# Esp32-S3-Mainboard.net
KiCad netlist of a schematic drawn in Altium Designer
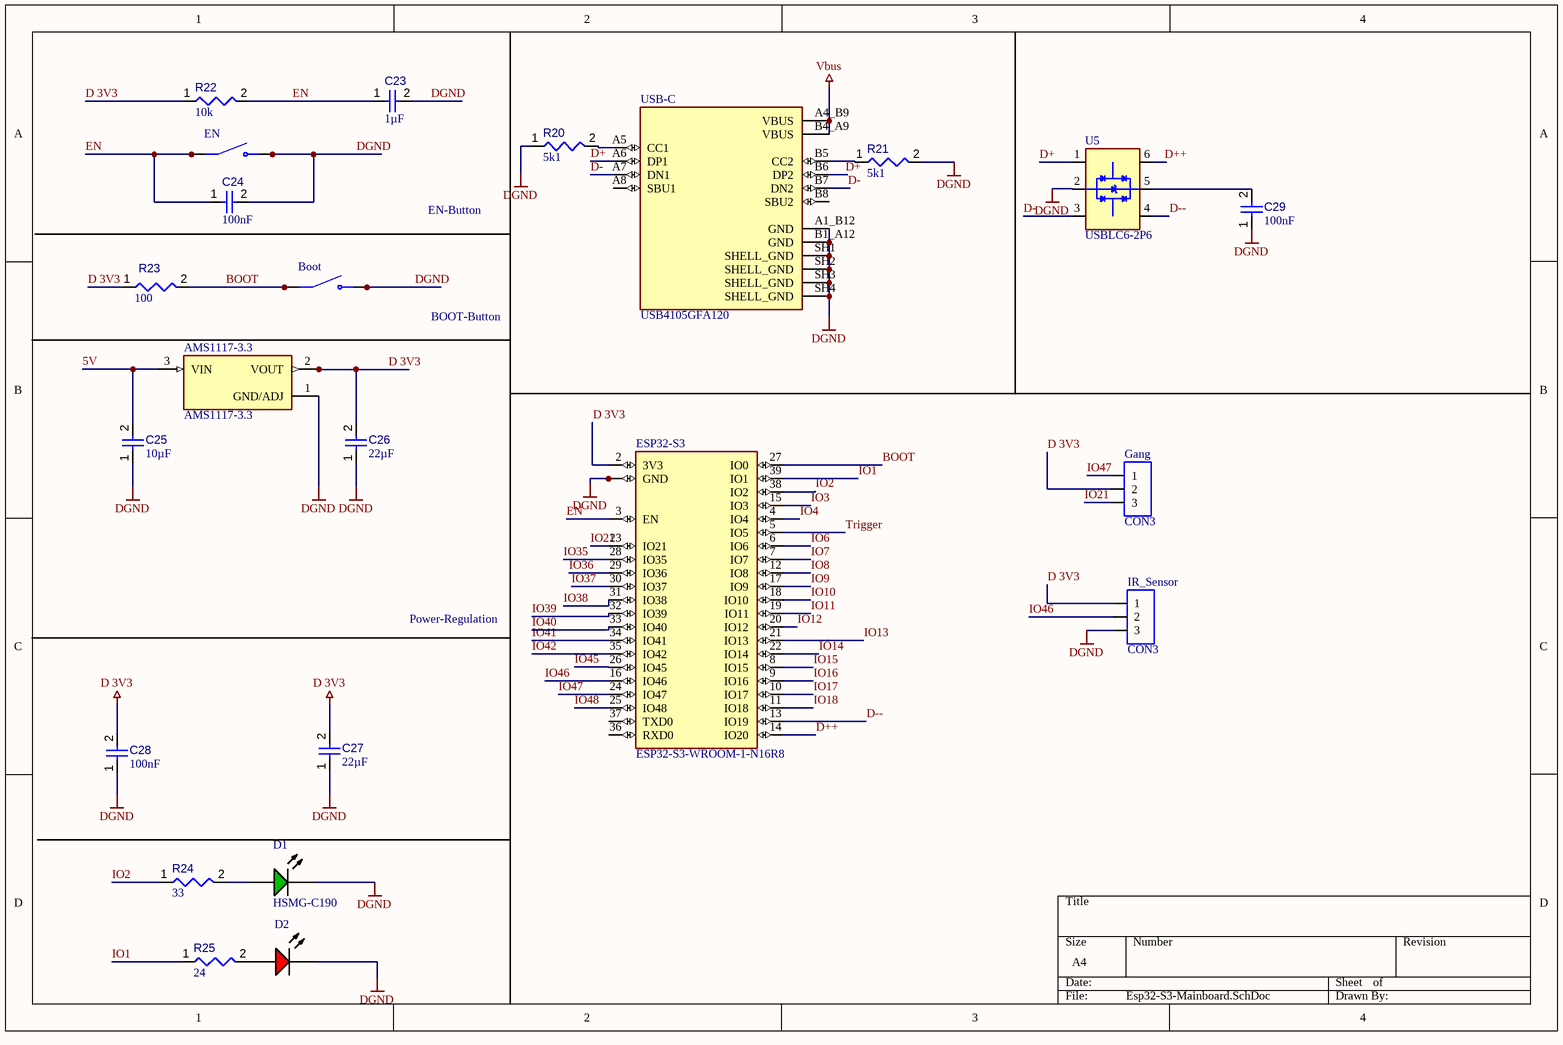
[diagram p0: Esp32-S3-Mainboard.SchDoc]

(export (version "E")
  (design (tool "Eeschema 10.0.6"))
  (components
    (comp (ref "AMS1117-3.3")
      (value "AMS1117-3.3")
      (footprint "SOT229P700X180-4N")
      (description "LDO Voltage Regulators 800MA LDO LINEAR REG")
      (fields (field (name "MF") "ams AG"))
      (libsource (lib "AMS1117-3.3") (part "AMS1117-3.3"))
    )
    (comp (ref "Boot")
      (value "FSM2JSMLTR")
      (footprint "SW_1571527-2")
      (description "Switch Tactile OFF (ON) SPST Round Button Gull Wing 0.05A 24VDC 0.98N SMD T/R")
      (fields (field (name "MF") "TE Connectivity"))
      (libsource (lib " L-PRAN") (part "FSM2JSMLTR"))
    )
    (comp (ref "C23")
      (value "1µF")
      (footprint "CAPC1608X90X35ML15T15")
      (description "Chip Capacitor, 1 uF, +/- 10%, 16 V, 0603 (1608 Metric)")
      (fields (field (name "TOLERANCE") "10%") (field (name "Comment") "Capacitor 1uF +/- 10% 16V 0603"))
      (libsource (lib " L-PRAN") (part "CAP-NP-2"))
    )
    (comp (ref "C24")
      (value "100nF")
      (footprint "CAPC1608X90X40NL10T20")
      (description "Chip Capacitor, 100 nF, +/- 10%, 50 V, 0603 (1608 Metric)")
      (fields (field (name "TOLERANCE") "10%") (field (name "Comment") "Capacitor 100 nF +/-10% 50 V 0603"))
      (libsource (lib " L-PRAN") (part "CAP-NP-2"))
    )
    (comp (ref "C25")
      (value "10µF")
      (footprint "CAPC0603(1608)100_L")
      (description "Chip Capacitor, 10µF +/-20%, 10V, 0603, Thickness 1 mm")
      (fields (field (name "TOLERANCE") "10%") (field (name "Comment") "Capacitor 10µF +/-20% 10V 0603"))
      (libsource (lib " L-PRAN") (part "CAP-NP-2"))
    )
    (comp (ref "C26")
      (value "22µF")
      (footprint "CAPC0805(2012)145_L")
      (description "Chip Capacitor, 22µF +/-40%, 16V, 0805, Thickness 1.45 mm")
      (fields (field (name "TOLERANCE") "5%") (field (name "Comment") "Capacitor 22µF +/-40% 16V 0805"))
      (libsource (lib " L-PRAN") (part "CAP-NP-2"))
    )
    (comp (ref "C27")
      (value "22µF")
      (footprint "CAPC0805(2012)145_L")
      (description "Chip Capacitor, 22µF +/-40%, 16V, 0805, Thickness 1.45 mm")
      (fields (field (name "TOLERANCE") "5%") (field (name "Comment") "Capacitor 22µF +/-40% 16V 0805"))
      (libsource (lib " L-PRAN") (part "CAP-NP-2"))
    )
    (comp (ref "C28")
      (value "100nF")
      (footprint "CAPC1608X90X40NL10T20")
      (description "Chip Capacitor, 100 nF, +/- 10%, 50 V, 0603 (1608 Metric)")
      (fields (field (name "TOLERANCE") "10%") (field (name "Comment") "Capacitor 100 nF +/-10% 50 V 0603"))
      (libsource (lib " L-PRAN") (part "CAP-NP-2"))
    )
    (comp (ref "C29")
      (value "100nF")
      (footprint "CAPC0402(1005)60_L")
      (description "Chip Capacitor, 100nF +/-20%, 50V, 0402, Thickness 0.6 mm")
      (fields (field (name "TOLERANCE") "10%") (field (name "Comment") "Capacitor 100nF +/-20% 50V 0402"))
      (libsource (lib " L-PRAN") (part "CAP-NP-2"))
    )
    (comp (ref "D1")
      (value "HSMG-C190")
      (footprint "AVAG-HSMX-C190_V")
      (description "LED Uni-Color Green, 52 mW, 20 mA, -40 to 85 degC, 2-Pin SMD, RoHS, Tape and Reel")
      (fields (field (name "POWER") "52mW") (field (name "MANUFACTURER") "Avago"))
      (libsource (lib " L-PRAN") (part "LED-GREEN-AK-2"))
    )
    (comp (ref "D2")
      (value "19-217/R6C-AL1M2VY/3T")
      (footprint "EVRL-0603-2_V")
      (description "Chip LED, Red, 5 V, 25 mA, -40 to 85 degC, 2-Pin SMD (0603), RoHS, Tape and Reel")
      (fields (field (name "MANUFACTURER") "Everlight Electronics"))
      (libsource (lib " L-PRAN") (part "LED-RED-AK-2"))
    )
    (comp (ref "EN")
      (value "FSM2JSMLTR")
      (footprint "SW_1571527-2")
      (description "Switch Tactile OFF (ON) SPST Round Button Gull Wing 0.05A 24VDC 0.98N SMD T/R")
      (fields (field (name "MF") "TE Connectivity"))
      (libsource (lib " L-PRAN") (part "FSM2JSMLTR"))
    )
    (comp (ref "ESP32-S3")
      (value "ESP32-S3-WROOM-1-N16R8")
      (footprint "ESP32S3WROOM1N8R2")
      (description "Bluetooth, WiFi 802.11b/g/n, Bluetooth v5.0 Transceiver Module 2.4GHz PCB Trace Surface Mount")
      (fields (field (name "MF") "Espressif Systems"))
      (libsource (lib "ESP32-S3-WROOM-1-N16R8") (part "ESP32-S3-WROOM-1-N16R8"))
    )
    (comp (ref "Gang")
      (value "CON3")
      (footprint "Sip-3")
      (description "Stecker")
      (libsource (lib "HTL-sym-2021_04") (part "CON3"))
    )
    (comp (ref "IR_Sensor")
      (value "CON3")
      (footprint "Sip-3")
      (description "Stecker")
      (libsource (lib "HTL-sym-2021_04") (part "CON3"))
    )
    (comp (ref "R20")
      (value "5k1")
      (footprint "RESC1608X55X25ML10T15")
      (description "Chip Resistor, 100 KOhm, +/- 1%, 0.1 W, -55 to 155 degC, 0603 (1608 Metric)")
      (fields (field (name "TOLERANCE") "1%") (field (name "POWER") "100mW"))
      (libsource (lib " L-PRAN") (part "RES-2"))
    )
    (comp (ref "R21")
      (value "5k1")
      (footprint "RESC1608X55X25ML10T15")
      (description "Chip Resistor, 100 KOhm, +/- 1%, 0.1 W, -55 to 155 degC, 0603 (1608 Metric)")
      (fields (field (name "TOLERANCE") "1%") (field (name "POWER") "100mW"))
      (libsource (lib " L-PRAN") (part "RES-2"))
    )
    (comp (ref "R22")
      (value "10k")
      (footprint "RESC1608X55X25ML10T15")
      (description "Chip Resistor, 10 KOhm, +/- 1%, 01 W, -55 to 155 degC, 0603 (1608 Metric)")
      (fields (field (name "POWER") "100mW") (field (name "TOLERANCE") "1%"))
      (libsource (lib " L-PRAN") (part "RES-2"))
    )
    (comp (ref "R23")
      (value "100")
      (footprint "RESC1608X55X25ML10T15")
      (description "Chip Resistor, 10 KOhm, +/- 1%, 01 W, -55 to 155 degC, 0603 (1608 Metric)")
      (fields (field (name "POWER") "100mW") (field (name "TOLERANCE") "1%"))
      (libsource (lib " L-PRAN") (part "RES-2"))
    )
    (comp (ref "R24")
      (value "33")
      (footprint "RESC1608X55X25ML10T15")
      (description "Chip Resistor, 10 KOhm, +/- 1%, 01 W, -55 to 155 degC, 0603 (1608 Metric)")
      (fields (field (name "POWER") "100mW") (field (name "TOLERANCE") "1%"))
      (libsource (lib " L-PRAN") (part "RES-2"))
    )
    (comp (ref "R25")
      (value "24")
      (footprint "RESC1608X55X25ML10T15")
      (description "Chip Resistor, 10 KOhm, +/- 1%, 01 W, -55 to 155 degC, 0603 (1608 Metric)")
      (fields (field (name "POWER") "100mW") (field (name "TOLERANCE") "1%"))
      (libsource (lib " L-PRAN") (part "RES-2"))
    )
    (comp (ref "U5")
      (value "USBLC6-2P6")
      (footprint "SOT50P160X60-6N")
      (description "17V Clamp 5A (8/20Âµs) Ipp Tvs Diode Surface Mount SOT-666")
      (fields (field (name "MF") "STMicroelectronics"))
      (libsource (lib "USBLC6-2P6") (part "USBLC6-2P6"))
    )
    (comp (ref "USB-C")
      (value "USB4105GFA120")
      (footprint "GCT_USB4105GFA120")
      (fields (field (name "MF") "Global Connector Technology"))
      (libsource (lib "USB4105GFA120") (part "USB4105GFA120"))
    )
  )
  (nets
    (net (code "1") (name "/5V") (class "Default")
      (node (ref "AMS1117-3.3") (pin "3") (pinfunction "VIN_3") (pintype "input"))
      (node (ref "C25") (pin "2") (pinfunction "2_2") (pintype "passive"))
    )
    (net (code "2") (name "/BOOT") (class "Default")
      (node (ref "Boot") (pin "1") (pinfunction "COM_1") (pintype "passive"))
      (node (ref "Boot") (pin "2") (pinfunction "COM_2") (pintype "passive"))
      (node (ref "ESP32-S3") (pin "27") (pinfunction "IO0_27") (pintype "bidirectional"))
      (node (ref "R23") (pin "2") (pinfunction "2_2") (pintype "passive"))
    )
    (net (code "3") (name "/D+") (class "Default")
      (node (ref "U5") (pin "1") (pinfunction "I/O1_1_1") (pintype "bidirectional"))
      (node (ref "USB-C") (pin "A6") (pinfunction "DP1_A6") (pintype "bidirectional"))
      (node (ref "USB-C") (pin "B6") (pinfunction "DP2_B6") (pintype "bidirectional"))
    )
    (net (code "4") (name "/D++") (class "Default")
      (node (ref "ESP32-S3") (pin "14") (pinfunction "IO20_14") (pintype "bidirectional"))
      (node (ref "U5") (pin "6") (pinfunction "I/O1_2_6") (pintype "bidirectional"))
    )
    (net (code "5") (name "/D-") (class "Default")
      (node (ref "U5") (pin "3") (pinfunction "I/O2_1_3") (pintype "bidirectional"))
      (node (ref "USB-C") (pin "A7") (pinfunction "DN1_A7") (pintype "bidirectional"))
      (node (ref "USB-C") (pin "B7") (pinfunction "DN2_B7") (pintype "bidirectional"))
    )
    (net (code "6") (name "/D--") (class "Default")
      (node (ref "ESP32-S3") (pin "13") (pinfunction "IO19_13") (pintype "bidirectional"))
      (node (ref "U5") (pin "4") (pinfunction "I/O2_2_4") (pintype "bidirectional"))
    )
    (net (code "7") (name "/EN") (class "Default")
      (node (ref "C23") (pin "1") (pinfunction "1_1") (pintype "passive"))
      (node (ref "C24") (pin "1") (pinfunction "1_1") (pintype "passive"))
      (node (ref "EN") (pin "1") (pinfunction "COM_1") (pintype "passive"))
      (node (ref "EN") (pin "2") (pinfunction "COM_2") (pintype "passive"))
      (node (ref "ESP32-S3") (pin "3") (pinfunction "EN_3") (pintype "bidirectional"))
      (node (ref "R22") (pin "2") (pinfunction "2_2") (pintype "passive"))
    )
    (net (code "8") (name "/IO1") (class "Default")
      (node (ref "ESP32-S3") (pin "39") (pinfunction "IO1_39") (pintype "bidirectional"))
      (node (ref "R25") (pin "1") (pinfunction "1_1") (pintype "passive"))
    )
    (net (code "9") (name "/IO2") (class "Default")
      (node (ref "ESP32-S3") (pin "38") (pinfunction "IO2_38") (pintype "bidirectional"))
      (node (ref "R24") (pin "1") (pinfunction "1_1") (pintype "passive"))
    )
    (net (code "10") (name "/IO3") (class "Default")
      (node (ref "ESP32-S3") (pin "15") (pinfunction "IO3_15") (pintype "bidirectional"))
    )
    (net (code "11") (name "/IO4") (class "Default")
      (node (ref "ESP32-S3") (pin "4") (pinfunction "IO4_4") (pintype "bidirectional"))
    )
    (net (code "12") (name "/IO6") (class "Default")
      (node (ref "ESP32-S3") (pin "6") (pinfunction "IO6_6") (pintype "bidirectional"))
    )
    (net (code "13") (name "/IO7") (class "Default")
      (node (ref "ESP32-S3") (pin "7") (pinfunction "IO7_7") (pintype "bidirectional"))
    )
    (net (code "14") (name "/IO8") (class "Default")
      (node (ref "ESP32-S3") (pin "12") (pinfunction "IO8_12") (pintype "bidirectional"))
    )
    (net (code "15") (name "/IO9") (class "Default")
      (node (ref "ESP32-S3") (pin "17") (pinfunction "IO9_17") (pintype "bidirectional"))
    )
    (net (code "16") (name "/IO10") (class "Default")
      (node (ref "ESP32-S3") (pin "18") (pinfunction "IO10_18") (pintype "bidirectional"))
    )
    (net (code "17") (name "/IO11") (class "Default")
      (node (ref "ESP32-S3") (pin "19") (pinfunction "IO11_19") (pintype "bidirectional"))
    )
    (net (code "18") (name "/IO12") (class "Default")
      (node (ref "ESP32-S3") (pin "20") (pinfunction "IO12_20") (pintype "bidirectional"))
    )
    (net (code "19") (name "/IO13") (class "Default")
      (node (ref "ESP32-S3") (pin "21") (pinfunction "IO13_21") (pintype "bidirectional"))
    )
    (net (code "20") (name "/IO14") (class "Default")
      (node (ref "ESP32-S3") (pin "22") (pinfunction "IO14_22") (pintype "bidirectional"))
    )
    (net (code "21") (name "/IO15") (class "Default")
      (node (ref "ESP32-S3") (pin "8") (pinfunction "IO15_8") (pintype "bidirectional"))
    )
    (net (code "22") (name "/IO16") (class "Default")
      (node (ref "ESP32-S3") (pin "9") (pinfunction "IO16_9") (pintype "bidirectional"))
    )
    (net (code "23") (name "/IO17") (class "Default")
      (node (ref "ESP32-S3") (pin "10") (pinfunction "IO17_10") (pintype "bidirectional"))
    )
    (net (code "24") (name "/IO18") (class "Default")
      (node (ref "ESP32-S3") (pin "11") (pinfunction "IO18_11") (pintype "bidirectional"))
    )
    (net (code "25") (name "/IO21") (class "Default")
      (node (ref "ESP32-S3") (pin "23") (pinfunction "IO21_23") (pintype "bidirectional"))
      (node (ref "Gang") (pin "3") (pinfunction "3_3") (pintype "passive"))
    )
    (net (code "26") (name "/IO35") (class "Default")
      (node (ref "ESP32-S3") (pin "28") (pinfunction "IO35_28") (pintype "bidirectional"))
    )
    (net (code "27") (name "/IO36") (class "Default")
      (node (ref "ESP32-S3") (pin "29") (pinfunction "IO36_29") (pintype "bidirectional"))
    )
    (net (code "28") (name "/IO37") (class "Default")
      (node (ref "ESP32-S3") (pin "30") (pinfunction "IO37_30") (pintype "bidirectional"))
    )
    (net (code "29") (name "/IO38") (class "Default")
      (node (ref "ESP32-S3") (pin "31") (pinfunction "IO38_31") (pintype "bidirectional"))
    )
    (net (code "30") (name "/IO39") (class "Default")
      (node (ref "ESP32-S3") (pin "32") (pinfunction "IO39_32") (pintype "bidirectional"))
    )
    (net (code "31") (name "/IO40") (class "Default")
      (node (ref "ESP32-S3") (pin "33") (pinfunction "IO40_33") (pintype "bidirectional"))
    )
    (net (code "32") (name "/IO41") (class "Default")
      (node (ref "ESP32-S3") (pin "34") (pinfunction "IO41_34") (pintype "bidirectional"))
    )
    (net (code "33") (name "/IO42") (class "Default")
      (node (ref "ESP32-S3") (pin "35") (pinfunction "IO42_35") (pintype "bidirectional"))
    )
    (net (code "34") (name "/IO45") (class "Default")
      (node (ref "ESP32-S3") (pin "26") (pinfunction "IO45_26") (pintype "bidirectional"))
    )
    (net (code "35") (name "/IO46") (class "Default")
      (node (ref "ESP32-S3") (pin "16") (pinfunction "IO46_16") (pintype "bidirectional"))
      (node (ref "IR_Sensor") (pin "2") (pinfunction "2_2") (pintype "passive"))
    )
    (net (code "36") (name "/IO47") (class "Default")
      (node (ref "ESP32-S3") (pin "24") (pinfunction "IO47_24") (pintype "bidirectional"))
      (node (ref "Gang") (pin "1") (pinfunction "1_1") (pintype "passive"))
    )
    (net (code "37") (name "/IO48") (class "Default")
      (node (ref "ESP32-S3") (pin "25") (pinfunction "IO48_25") (pintype "bidirectional"))
    )
    (net (code "38") (name "/Trigger") (class "Default")
      (node (ref "ESP32-S3") (pin "5") (pinfunction "IO5_5") (pintype "bidirectional"))
    )
    (net (code "39") (name "D 3V3") (class "Default")
      (node (ref "AMS1117-3.3") (pin "2") (pinfunction "VOUT_2") (pintype "output"))
      (node (ref "C26") (pin "2") (pinfunction "2_2") (pintype "passive"))
      (node (ref "C27") (pin "2") (pinfunction "2_2") (pintype "passive"))
      (node (ref "C28") (pin "2") (pinfunction "2_2") (pintype "passive"))
      (node (ref "ESP32-S3") (pin "2") (pinfunction "3V3_2") (pintype "bidirectional"))
      (node (ref "Gang") (pin "2") (pinfunction "2_2") (pintype "passive"))
      (node (ref "IR_Sensor") (pin "1") (pinfunction "1_1") (pintype "passive"))
      (node (ref "R22") (pin "1") (pinfunction "1_1") (pintype "passive"))
      (node (ref "R23") (pin "1") (pinfunction "1_1") (pintype "passive"))
    )
    (net (code "40") (name "DGND") (class "Default")
      (node (ref "AMS1117-3.3") (pin "1") (pinfunction "GND/ADJ_1") (pintype "power_in"))
      (node (ref "Boot") (pin "3") (pinfunction "NO_3") (pintype "passive"))
      (node (ref "Boot") (pin "4") (pinfunction "NO_4") (pintype "passive"))
      (node (ref "C23") (pin "2") (pinfunction "2_2") (pintype "passive"))
      (node (ref "C24") (pin "2") (pinfunction "2_2") (pintype "passive"))
      (node (ref "C25") (pin "1") (pinfunction "1_1") (pintype "passive"))
      (node (ref "C26") (pin "1") (pinfunction "1_1") (pintype "passive"))
      (node (ref "C27") (pin "1") (pinfunction "1_1") (pintype "passive"))
      (node (ref "C28") (pin "1") (pinfunction "1_1") (pintype "passive"))
      (node (ref "C29") (pin "1") (pinfunction "1_1") (pintype "passive"))
      (node (ref "D1") (pin "2") (pinfunction "K_2") (pintype "passive"))
      (node (ref "D2") (pin "2") (pinfunction "K_2") (pintype "passive"))
      (node (ref "EN") (pin "3") (pinfunction "NO_3") (pintype "passive"))
      (node (ref "EN") (pin "4") (pinfunction "NO_4") (pintype "passive"))
      (node (ref "ESP32-S3") (pin "1") (pinfunction "GND_1") (pintype "bidirectional"))
      (node (ref "ESP32-S3") (pin "40") (pinfunction "GND_40") (pintype "bidirectional"))
      (node (ref "ESP32-S3") (pin "41") (pinfunction "GND_41") (pintype "bidirectional"))
      (node (ref "ESP32-S3") (pin "42") (pinfunction "GND_42") (pintype "bidirectional"))
      (node (ref "ESP32-S3") (pin "43") (pinfunction "GND_43") (pintype "bidirectional"))
      (node (ref "ESP32-S3") (pin "44") (pinfunction "GND_44") (pintype "bidirectional"))
      (node (ref "ESP32-S3") (pin "45") (pinfunction "GND_45") (pintype "bidirectional"))
      (node (ref "ESP32-S3") (pin "46") (pinfunction "GND_46") (pintype "bidirectional"))
      (node (ref "ESP32-S3") (pin "47") (pinfunction "GND_47") (pintype "bidirectional"))
      (node (ref "ESP32-S3") (pin "48") (pinfunction "GND_48") (pintype "bidirectional"))
      (node (ref "ESP32-S3") (pin "49") (pinfunction "GND_49") (pintype "bidirectional"))
      (node (ref "IR_Sensor") (pin "3") (pinfunction "3_3") (pintype "passive"))
      (node (ref "R20") (pin "1") (pinfunction "1_1") (pintype "passive"))
      (node (ref "R21") (pin "2") (pinfunction "2_2") (pintype "passive"))
      (node (ref "U5") (pin "2") (pinfunction "GND_2") (pintype "power_in"))
      (node (ref "USB-C") (pin "A1_B12") (pinfunction "GND_A1_B12") (pintype "power_in"))
      (node (ref "USB-C") (pin "B1_A12") (pinfunction "GND_B1_A12") (pintype "power_in"))
      (node (ref "USB-C") (pin "SH1") (pinfunction "SHELL_GND_SH1") (pintype "power_in"))
      (node (ref "USB-C") (pin "SH2") (pinfunction "SHELL_GND_SH2") (pintype "power_in"))
      (node (ref "USB-C") (pin "SH3") (pinfunction "SHELL_GND_SH3") (pintype "power_in"))
      (node (ref "USB-C") (pin "SH4") (pinfunction "SHELL_GND_SH4") (pintype "power_in"))
    )
    (net (code "41") (name "Net-(D1-A)") (class "Default")
      (node (ref "D1") (pin "1") (pinfunction "A_1") (pintype "passive"))
      (node (ref "R24") (pin "2") (pinfunction "2_2") (pintype "passive"))
    )
    (net (code "42") (name "Net-(D2-A)") (class "Default")
      (node (ref "D2") (pin "1") (pinfunction "A_1") (pintype "passive"))
      (node (ref "R25") (pin "2") (pinfunction "2_2") (pintype "passive"))
    )
    (net (code "43") (name "Net-(U5-VBUS)") (class "Default")
      (node (ref "C29") (pin "2") (pinfunction "2_2") (pintype "passive"))
      (node (ref "U5") (pin "5") (pinfunction "VBUS_5") (pintype "power_in"))
    )
    (net (code "44") (name "Net-(USB-C-CC1)") (class "Default")
      (node (ref "R20") (pin "2") (pinfunction "2_2") (pintype "passive"))
      (node (ref "USB-C") (pin "A5") (pinfunction "CC1_A5") (pintype "bidirectional"))
    )
    (net (code "45") (name "Net-(USB-C-CC2)") (class "Default")
      (node (ref "R21") (pin "1") (pinfunction "1_1") (pintype "passive"))
      (node (ref "USB-C") (pin "B5") (pinfunction "CC2_B5") (pintype "bidirectional"))
    )
    (net (code "46") (name "Vbus") (class "Default")
      (node (ref "USB-C") (pin "A4_B9") (pinfunction "VBUS_A4_B9") (pintype "power_in"))
      (node (ref "USB-C") (pin "B4_A9") (pinfunction "VBUS_B4_A9") (pintype "power_in"))
    )
    (net (code "47") (name "unconnected-(ESP32-S3-RXD0-Pad36)") (class "Default")
      (node (ref "ESP32-S3") (pin "36") (pinfunction "RXD0_36") (pintype "bidirectional"))
    )
    (net (code "48") (name "unconnected-(ESP32-S3-TXD0-Pad37)") (class "Default")
      (node (ref "ESP32-S3") (pin "37") (pinfunction "TXD0_37") (pintype "bidirectional"))
    )
    (net (code "49") (name "unconnected-(USB-C-SBU1-PadA8)") (class "Default")
      (node (ref "USB-C") (pin "A8") (pinfunction "SBU1_A8") (pintype "bidirectional"))
    )
    (net (code "50") (name "unconnected-(USB-C-SBU2-PadB8)") (class "Default")
      (node (ref "USB-C") (pin "B8") (pinfunction "SBU2_B8") (pintype "bidirectional"))
    )
  )
)
